# PAM8016-breakout.net
KiCad netlist of a schematic drawn in EAGLE
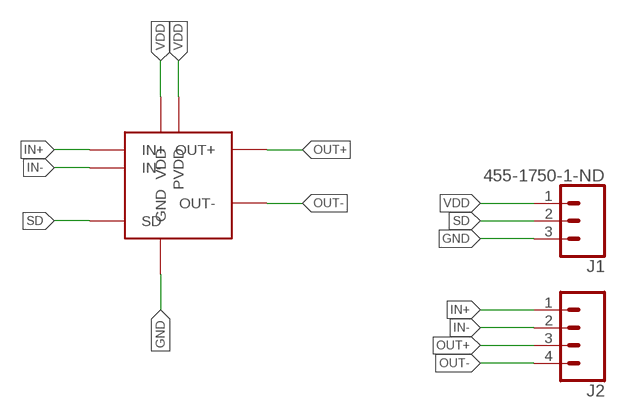
[diagram p0: schematic, sheet 1]

(export (version "E")
  (design (tool "Eeschema 10.0.6"))
  (components
    (comp (ref "J1")
      (value "455-1750-1-ND")
      (footprint "eagle-import:1X03")
      (libsource (lib "eagle-import") (part "CONN_03"))
    )
    (comp (ref "J2")
      (value "CONN_04")
      (footprint "eagle-import:1X04")
      (libsource (lib "eagle-import") (part "CONN_04"))
    )
    (comp (ref "U$1")
      (value "PAM8016")
      (footprint "eagle-import:U-FLGA1515-9")
      (libsource (lib "eagle-import") (part "PAM8016"))
    )
  )
  (nets
    (net (code "1") (name "GND") (class "Default")
      (node (ref "J1") (pin "3") (pinfunction "3_3") (pintype "passive"))
      (node (ref "U$1") (pin "A2") (pinfunction "GND_A2") (pintype "bidirectional"))
      (node (ref "U$1") (pin "B3") (pinfunction "GND_B3") (pintype "bidirectional"))
    )
    (net (code "2") (name "IN+") (class "Default")
      (node (ref "J2") (pin "1") (pinfunction "1_1") (pintype "passive"))
      (node (ref "U$1") (pin "A1") (pinfunction "IN+_A1") (pintype "bidirectional"))
    )
    (net (code "3") (name "IN-") (class "Default")
      (node (ref "J2") (pin "2") (pinfunction "2_2") (pintype "passive"))
      (node (ref "U$1") (pin "C1") (pinfunction "IN-_C1") (pintype "bidirectional"))
    )
    (net (code "4") (name "OUT+") (class "Default")
      (node (ref "J2") (pin "3") (pinfunction "3_3") (pintype "passive"))
      (node (ref "U$1") (pin "C3") (pinfunction "OUT+_C3") (pintype "bidirectional"))
    )
    (net (code "5") (name "OUT-") (class "Default")
      (node (ref "J2") (pin "4") (pinfunction "4_4") (pintype "passive"))
      (node (ref "U$1") (pin "A3") (pinfunction "OUT-_A3") (pintype "bidirectional"))
    )
    (net (code "6") (name "SD") (class "Default")
      (node (ref "J1") (pin "2") (pinfunction "2_2") (pintype "passive"))
      (node (ref "U$1") (pin "C2") (pinfunction "SD_C2") (pintype "bidirectional"))
    )
    (net (code "7") (name "VDD") (class "Default")
      (node (ref "J1") (pin "1") (pinfunction "1_1") (pintype "passive"))
      (node (ref "U$1") (pin "B1") (pinfunction "VDD_B1") (pintype "bidirectional"))
      (node (ref "U$1") (pin "B2") (pinfunction "PVDD_B2") (pintype "bidirectional"))
    )
  )
)
